# CW.net
KiCad netlist of a schematic drawn in Altium Designer
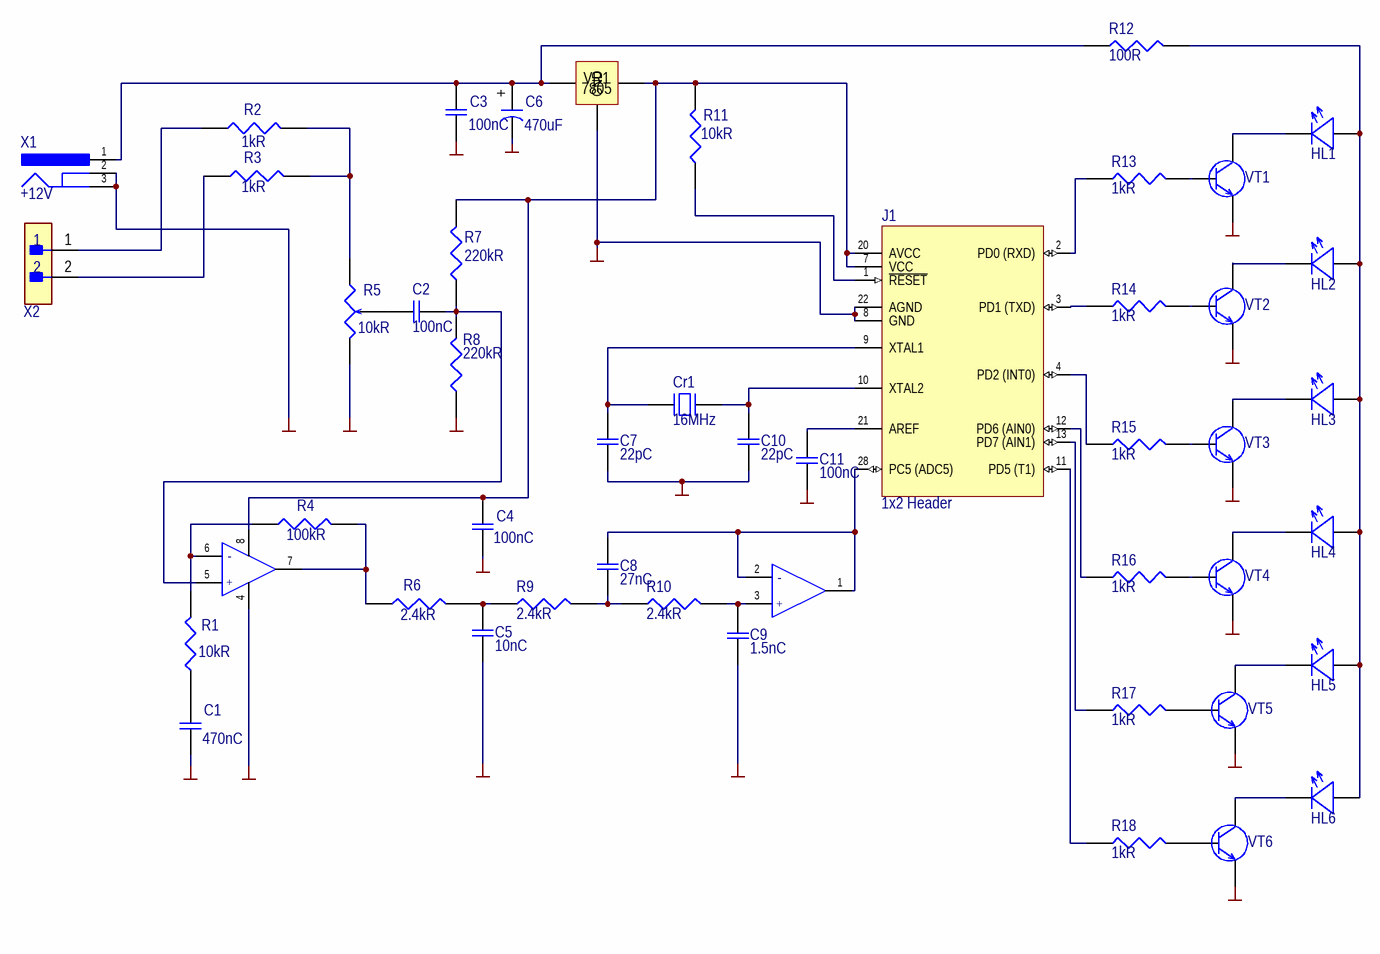
[diagram p0: CW.SchDoc]

(export (version "E")
  (design (tool "Eeschema 10.0.6"))
  (components
    (comp (ref "C1")
      (value "470nC")
      (footprint "C470nF")
      (description "CAP, X7R, 470NF, 16V, 0805, FULL REEL")
      (fields
        (field (name "MANUFACTURER") "Kyocera AVX")
        (field (name "MANUFACTURER PART NUMBER") "0805YC474KAT2A")
      )
      (libsource (lib "CW_Schlib") (part "C0805YC474KAT2A"))
    )
    (comp (ref "C2")
      (value "100nC")
      (footprint "C100nF")
      (description "CAP CER 0.1UF 16V 20% Y5V 0805")
      (fields
        (field (name "MANUFACTURER") "KEMET")
        (field (name "MANUFACTURER PART NUMBER") "C0805C104M4VACTU")
      )
      (libsource (lib "CW_Schlib") (part "C0805C104M4VACTU"))
    )
    (comp (ref "C3")
      (value "100nC")
      (footprint "C100nF")
      (description "CAP CER 0.1UF 16V 20% Y5V 0805")
      (fields
        (field (name "MANUFACTURER") "KEMET")
        (field (name "MANUFACTURER PART NUMBER") "C0805C104M4VACTU")
      )
      (libsource (lib "CW_Schlib") (part "C0805C104M4VACTU"))
    )
    (comp (ref "C4")
      (value "100nC")
      (footprint "C100nF")
      (description "CAP CER 0.1UF 16V 20% Y5V 0805")
      (fields
        (field (name "MANUFACTURER") "KEMET")
        (field (name "MANUFACTURER PART NUMBER") "C0805C104M4VACTU")
      )
      (libsource (lib "CW_Schlib") (part "C0805C104M4VACTU"))
    )
    (comp (ref "C5")
      (value "10nC")
      (footprint "C10nF")
      (description "CAP CER 10000PF 16V X7R 0402")
      (fields
        (field (name "MANUFACTURER") "Yageo")
        (field (name "MANUFACTURER PART NUMBER") "CC0402KRX7R7BB103")
      )
      (libsource (lib "CW_Schlib") (part "CC0402KRX7R7BB103"))
    )
    (comp (ref "C6")
      (value "470uF")
      (footprint "ElectrolyticCap")
      (fields
        (field (name "MANUFACTURER") "Panasonic")
        (field (name "MANUFACTURER PART NUMBER") "EEEFK1C471P")
        (field (name "TOLERANCE") "20%")
      )
      (libsource (lib "CW_Schlib") (part "EEEFK1C471P"))
    )
    (comp (ref "C7")
      (value "22pC")
      (footprint "C22pF")
      (description "1206 22pF Ceramic Multilayer Capacitor; 50VDC; 125degC; C0G Dielec; +/-5% SMD")
      (fields
        (field (name "MANUFACTURER") "KEMET")
        (field (name "MANUFACTURER PART NUMBER") "C1206C220J5GACTU")
      )
      (libsource (lib "CW_Schlib") (part "C1206C220J5GACTU"))
    )
    (comp (ref "C8")
      (value "27nC")
      (footprint "C27nF")
      (description "CAP CER 0.027UF 50V X7R 0805")
      (fields
        (field (name "MANUFACTURER") "KEMET")
        (field (name "MANUFACTURER PART NUMBER") "C0805C273K5RACTU")
      )
      (libsource (lib "CW_Schlib") (part "C0805C273K5RACTU"))
    )
    (comp (ref "C9")
      (value "1.5nC")
      (footprint "C1.5nF")
      (description "0805 1.5nF Ceramic Multilayer Capacitor,  100 VDC,  +125degC,  X7R Dielec,  +/-10%")
      (fields
        (field (name "MANUFACTURER") "Kyocera AVX")
        (field (name "MANUFACTURER PART NUMBER") "08051C152KAT2A")
      )
      (libsource (lib "CW_Schlib") (part "C08051C152KAT2A"))
    )
    (comp (ref "C10")
      (value "22pC")
      (footprint "C22pF")
      (description "1206 22pF Ceramic Multilayer Capacitor; 50VDC; 125degC; C0G Dielec; +/-5% SMD")
      (fields
        (field (name "MANUFACTURER") "KEMET")
        (field (name "MANUFACTURER PART NUMBER") "C1206C220J5GACTU")
      )
      (libsource (lib "CW_Schlib") (part "C1206C220J5GACTU"))
    )
    (comp (ref "C11")
      (value "100nC")
      (footprint "C100nF")
      (description "CAP CER 0.1UF 16V 20% Y5V 0805")
      (fields
        (field (name "MANUFACTURER") "KEMET")
        (field (name "MANUFACTURER PART NUMBER") "C0805C104M4VACTU")
      )
      (libsource (lib "CW_Schlib") (part "C0805C104M4VACTU"))
    )
    (comp (ref "Cr1")
      (value "16MHz")
      (footprint "Crystal")
      (description "CRYSTAL 16.0MHZ 20PF SMD")
      (fields (field (name "MANUFACTURER") "CTS") (field (name "MANUFACTURER PART NUMBER") "ATS16ASM-1"))
      (libsource (lib "CW_Schlib") (part "ATS16ASM-1"))
    )
    (comp (ref "DA1")
      (value "Amplifier (part B)")
      (footprint "LM358")
      (description "TEXAS INSTRUMENTS   LM358N/NOPB..   OP AMP, 1MHZ, 0.1V/S, 7MV, DIP8")
      (fields
        (field (name "MANUFACTURER") "TI National Semiconductor")
        (field (name "MANUFACTURER PART NUMBER") "LM358N/NOPB")
      )
      (libsource (lib "CW_Schlib") (part "LM358N/NOPB (1)"))
    )
    (comp (ref "DA2")
      (value "5V")
      (footprint "LM7805")
      (description "Series 3-Terminal Positive Regulators")
      (fields
        (field (name "MANUFACTURER") "Texas Instruments")
        (field (name "MANUFACTURER PART NUMBER") "LM7805CT/NOPB")
      )
      (libsource (lib "CW_Schlib") (part "LM7805CT/NOPB"))
    )
    (comp (ref "HL1")
      (value "red led")
      (footprint "LEDred")
      (description "WURTH ELEKTRONIK - 151051RS11000 - LED, Red, Through Hole, T-1 3/4 (5mm), 30 mA, 2.1 V, 630 nm")
      (fields
        (field (name "MANUFACTURER") "Wurth Electronics")
        (field (name "MANUFACTURER PART NUMBER") "151051RS11000")
      )
      (libsource (lib "CW_Schlib") (part "151051RS11000"))
    )
    (comp (ref "HL2")
      (value "blue led")
      (footprint "LEDblue")
      (description "WURTH ELEKTRONIK - 151051BS04000 - LED, 5MM, BLUE, 500MCD, 470NM")
      (fields
        (field (name "MANUFACTURER") "Wurth Electronics")
        (field (name "MANUFACTURER PART NUMBER") "151051BS04000")
      )
      (libsource (lib "CW_Schlib") (part "151051BS04000"))
    )
    (comp (ref "HL3")
      (value "red led")
      (footprint "LEDred")
      (description "WURTH ELEKTRONIK - 151051RS11000 - LED, Red, Through Hole, T-1 3/4 (5mm), 30 mA, 2.1 V, 630 nm")
      (fields
        (field (name "MANUFACTURER") "Wurth Electronics")
        (field (name "MANUFACTURER PART NUMBER") "151051RS11000")
      )
      (libsource (lib "CW_Schlib") (part "151051RS11000"))
    )
    (comp (ref "HL4")
      (value "green led")
      (footprint "LEDgreen")
      (description "WURTH ELEKTRONIK - 151051VS04000 - LED, Green, Through Hole, T-1 3/4 (5mm), 30 mA, 2.1 V, 572 nm")
      (fields
        (field (name "MANUFACTURER") "Wurth Electronics")
        (field (name "MANUFACTURER PART NUMBER") "151051VS04000")
      )
      (libsource (lib "CW_Schlib") (part "151051VS04000"))
    )
    (comp (ref "HL5")
      (value "yellow led")
      (footprint "LEDyellow")
      (description "WURTH ELEKTRONIK - 151051YS04000 - LED, Yellow, Through Hole, T-1 3/4 (5mm), 30 mA, 2 V, 590 nm")
      (fields
        (field (name "MANUFACTURER") "Wurth Electronics")
        (field (name "MANUFACTURER PART NUMBER") "151051YS04000")
      )
      (libsource (lib "CW_Schlib") (part "151051YS04000"))
    )
    (comp (ref "HL6")
      (value "green led")
      (footprint "LEDgreen")
      (description "WURTH ELEKTRONIK - 151051VS04000 - LED, Green, Through Hole, T-1 3/4 (5mm), 30 mA, 2.1 V, 572 nm")
      (fields
        (field (name "MANUFACTURER") "Wurth Electronics")
        (field (name "MANUFACTURER PART NUMBER") "151051VS04000")
      )
      (libsource (lib "CW_Schlib") (part "151051VS04000"))
    )
    (comp (ref "J1")
      (value "1x2 Header")
      (footprint "ATmega8")
      (description "MCU 8-bit ATmega AVR RISC 8KB Flash 3.3V/5V 28-Pin PDIP")
      (fields
        (field (name "MANUFACTURER") "Microchip / Atmel")
        (field (name "MANUFACTURER PART NUMBER") "ATMEGA8A-PU")
      )
      (libsource (lib "CW_Schlib") (part "ATMEGA8A-PU"))
    )
    (comp (ref "R1")
      (value "10kR")
      (footprint "R10kOhm")
      (description "Res Thick Film 0805 10K Ohm 5% 1/8W ±200ppm/°C Molded SMD Paper T/R")
      (fields
        (field (name "MANUFACTURER") "Vishay Semiconductors")
        (field (name "MANUFACTURER PART NUMBER") "CRCW080510K0JNEAC")
      )
      (libsource (lib "CW_Schlib") (part "CRCW080510K0JNEAC"))
    )
    (comp (ref "R2")
      (value "1kR")
      (footprint "R1kOhm")
      (description "Res Thick Film 0805 1K Ohm 5% 1/8W 200ppm/C Molded SMD SMD Paper T/R")
      (fields
        (field (name "MANUFACTURER") "Vishay Dale")
        (field (name "MANUFACTURER PART NUMBER") "CRCW08051K00JNEA")
      )
      (libsource (lib "CW_Schlib") (part "CRCW08051K00JNEA"))
    )
    (comp (ref "R3")
      (value "1kR")
      (footprint "R1kOhm")
      (description "Res Thick Film 0805 1K Ohm 5% 1/8W 200ppm/C Molded SMD SMD Paper T/R")
      (fields
        (field (name "MANUFACTURER") "Vishay Dale")
        (field (name "MANUFACTURER PART NUMBER") "CRCW08051K00JNEA")
      )
      (libsource (lib "CW_Schlib") (part "CRCW08051K00JNEA"))
    )
    (comp (ref "R4")
      (value "100kR")
      (footprint "R100kOhm")
      (description "Res Thick Film 0805 100K Ohm 5% 1/8W 200ppm/C Molded SMD SMD Paper T/R")
      (fields
        (field (name "MANUFACTURER") "Vishay Dale")
        (field (name "MANUFACTURER PART NUMBER") "CRCW0805100KJNEB")
      )
      (libsource (lib "CW_Schlib") (part "CRCW0805100KJNEB"))
    )
    (comp (ref "R5")
      (value "10kR")
      (footprint "Potentiometer")
      (description "BOURNS 3313J-1-103E             TRIMMER, 10KOHM, 125mW, SMD")
      (fields (field (name "MANUFACTURER") "Bourns") (field (name "MANUFACTURER PART NUMBER") "3313J-1-103E"))
      (libsource (lib "CW_Schlib") (part "3313J-1-103E"))
    )
    (comp (ref "R6")
      (value "2.4kR")
      (footprint "R2.4kohm")
      (description "Resistor,Metal Glaze,2.4KOhms,150WV,5+/-% Tol,-200,200ppm-TC,0805-Case ;RoHS Compliant: Yes")
      (fields
        (field (name "MANUFACTURER") "Vishay Dale")
        (field (name "MANUFACTURER PART NUMBER") "CRCW08052K40JNEA")
      )
      (libsource (lib "CW_Schlib") (part "CRCW08052K40JNEA"))
    )
    (comp (ref "R7")
      (value "220kR")
      (footprint "R220kOhm")
      (description "RES SMD 220K OHM 5% 1/8W 0805")
      (fields
        (field (name "MANUFACTURER") "Vishay Dale")
        (field (name "MANUFACTURER PART NUMBER") "CRCW0805220KJNEA")
      )
      (libsource (lib "CW_Schlib") (part "CRCW0805220KJNEA"))
    )
    (comp (ref "R8")
      (value "220kR")
      (footprint "R220kOhm")
      (description "RES SMD 220K OHM 5% 1/8W 0805")
      (fields
        (field (name "MANUFACTURER") "Vishay Dale")
        (field (name "MANUFACTURER PART NUMBER") "CRCW0805220KJNEA")
      )
      (libsource (lib "CW_Schlib") (part "CRCW0805220KJNEA"))
    )
    (comp (ref "R9")
      (value "2.4kR")
      (footprint "R2.4kohm")
      (description "Resistor,Metal Glaze,2.4KOhms,150WV,5+/-% Tol,-200,200ppm-TC,0805-Case ;RoHS Compliant: Yes")
      (fields
        (field (name "MANUFACTURER") "Vishay Dale")
        (field (name "MANUFACTURER PART NUMBER") "CRCW08052K40JNEA")
      )
      (libsource (lib "CW_Schlib") (part "CRCW08052K40JNEA"))
    )
    (comp (ref "R10")
      (value "2.4kR")
      (footprint "R2.4kohm")
      (description "Resistor,Metal Glaze,2.4KOhms,150WV,5+/-% Tol,-200,200ppm-TC,0805-Case ;RoHS Compliant: Yes")
      (fields
        (field (name "MANUFACTURER") "Vishay Dale")
        (field (name "MANUFACTURER PART NUMBER") "CRCW08052K40JNEA")
      )
      (libsource (lib "CW_Schlib") (part "CRCW08052K40JNEA"))
    )
    (comp (ref "R11")
      (value "10kR")
      (footprint "R10kOhm")
      (description "Res Thick Film 0805 10K Ohm 5% 1/8W ±200ppm/°C Molded SMD Paper T/R")
      (fields
        (field (name "MANUFACTURER") "Vishay Semiconductors")
        (field (name "MANUFACTURER PART NUMBER") "CRCW080510K0JNEAC")
      )
      (libsource (lib "CW_Schlib") (part "CRCW080510K0JNEAC"))
    )
    (comp (ref "R12")
      (value "100R")
      (footprint "R100Ohm")
      (fields
        (field (name "MANUFACTURER") "Panasonic")
        (field (name "MANUFACTURER PART NUMBER") "ERA-6AEB101V")
        (field (name "TOLERANCE") "0.1%")
      )
      (libsource (lib "CW_Schlib") (part "ERA-6AEB101V"))
    )
    (comp (ref "R13")
      (value "1kR")
      (footprint "R1kOhm")
      (description "Res Thick Film 0805 1K Ohm 5% 1/8W 200ppm/C Molded SMD SMD Paper T/R")
      (fields
        (field (name "MANUFACTURER") "Vishay Dale")
        (field (name "MANUFACTURER PART NUMBER") "CRCW08051K00JNEA")
      )
      (libsource (lib "CW_Schlib") (part "CRCW08051K00JNEA"))
    )
    (comp (ref "R14")
      (value "1kR")
      (footprint "R1kOhm")
      (description "Res Thick Film 0805 1K Ohm 5% 1/8W 200ppm/C Molded SMD SMD Paper T/R")
      (fields
        (field (name "MANUFACTURER") "Vishay Dale")
        (field (name "MANUFACTURER PART NUMBER") "CRCW08051K00JNEA")
      )
      (libsource (lib "CW_Schlib") (part "CRCW08051K00JNEA"))
    )
    (comp (ref "R15")
      (value "1kR")
      (footprint "R1kOhm")
      (description "Res Thick Film 0805 1K Ohm 5% 1/8W 200ppm/C Molded SMD SMD Paper T/R")
      (fields
        (field (name "MANUFACTURER") "Vishay Dale")
        (field (name "MANUFACTURER PART NUMBER") "CRCW08051K00JNEA")
      )
      (libsource (lib "CW_Schlib") (part "CRCW08051K00JNEA"))
    )
    (comp (ref "R16")
      (value "1kR")
      (footprint "R1kOhm")
      (description "Res Thick Film 0805 1K Ohm 5% 1/8W 200ppm/C Molded SMD SMD Paper T/R")
      (fields
        (field (name "MANUFACTURER") "Vishay Dale")
        (field (name "MANUFACTURER PART NUMBER") "CRCW08051K00JNEA")
      )
      (libsource (lib "CW_Schlib") (part "CRCW08051K00JNEA"))
    )
    (comp (ref "R17")
      (value "1kR")
      (footprint "R1kOhm")
      (description "Res Thick Film 0805 1K Ohm 5% 1/8W 200ppm/C Molded SMD SMD Paper T/R")
      (fields
        (field (name "MANUFACTURER") "Vishay Dale")
        (field (name "MANUFACTURER PART NUMBER") "CRCW08051K00JNEA")
      )
      (libsource (lib "CW_Schlib") (part "CRCW08051K00JNEA"))
    )
    (comp (ref "R18")
      (value "1kR")
      (footprint "R1kOhm")
      (description "Res Thick Film 0805 1K Ohm 5% 1/8W 200ppm/C Molded SMD SMD Paper T/R")
      (fields
        (field (name "MANUFACTURER") "Vishay Dale")
        (field (name "MANUFACTURER PART NUMBER") "CRCW08051K00JNEA")
      )
      (libsource (lib "CW_Schlib") (part "CRCW08051K00JNEA"))
    )
    (comp (ref "VT1")
      (value "BC639")
      (footprint "BC639")
      (description "TRANS NPN 80V 1A TO-92")
      (fields (field (name "MANUFACTURER") "ON Semiconductor / Fairchild"))
      (libsource (lib "CW_Schlib") (part "BC639"))
    )
    (comp (ref "VT2")
      (value "BC639")
      (footprint "BC639")
      (description "TRANS NPN 80V 1A TO-92")
      (fields (field (name "MANUFACTURER") "ON Semiconductor / Fairchild"))
      (libsource (lib "CW_Schlib") (part "BC639"))
    )
    (comp (ref "VT3")
      (value "BC639")
      (footprint "BC639")
      (description "TRANS NPN 80V 1A TO-92")
      (fields (field (name "MANUFACTURER") "ON Semiconductor / Fairchild"))
      (libsource (lib "CW_Schlib") (part "BC639"))
    )
    (comp (ref "VT4")
      (value "BC639")
      (footprint "BC639")
      (description "TRANS NPN 80V 1A TO-92")
      (fields (field (name "MANUFACTURER") "ON Semiconductor / Fairchild"))
      (libsource (lib "CW_Schlib") (part "BC639"))
    )
    (comp (ref "VT5")
      (value "BC639")
      (footprint "BC639")
      (description "TRANS NPN 80V 1A TO-92")
      (fields (field (name "MANUFACTURER") "ON Semiconductor / Fairchild"))
      (libsource (lib "CW_Schlib") (part "BC639"))
    )
    (comp (ref "VT6")
      (value "BC639")
      (footprint "BC639")
      (description "TRANS NPN 80V 1A TO-92")
      (fields (field (name "MANUFACTURER") "ON Semiconductor / Fairchild"))
      (libsource (lib "CW_Schlib") (part "BC639"))
    )
    (comp (ref "X1")
      (value "+12V")
      (footprint "PG_Connector")
      (description "KYCON - KLDX-0202-A - DC Power Connector, Jack, 3.5 A, 2 mm, PCB Mount, Through Hole")
      (fields (field (name "MANUFACTURER") "Kycon") (field (name "MANUFACTURER PART NUMBER") "KLDX-0202-A"))
      (libsource (lib "CW_Schlib") (part "KLDX-0202-A"))
    )
    (comp (ref "X2")
      (value "ConnectorAudio")
      (footprint "AudioConnector")
      (fields (field (name "MANUFACTURER") "Molex") (field (name "MANUFACTURER PART NUMBER") "43650-0229"))
      (libsource (lib "CW_Schlib") (part "43650-0229"))
    )
  )
  (nets
    (net (code "1") (name "GND") (class "Default")
      (node (ref "C1") (pin "1") (pinfunction "1_1") (pintype "passive"))
      (node (ref "C10") (pin "1") (pinfunction "1_1") (pintype "passive"))
      (node (ref "C11") (pin "1") (pinfunction "1_1") (pintype "passive"))
      (node (ref "C3") (pin "1") (pinfunction "1_1") (pintype "passive"))
      (node (ref "C4") (pin "1") (pinfunction "1_1") (pintype "passive"))
      (node (ref "C5") (pin "1") (pinfunction "1_1") (pintype "passive"))
      (node (ref "C6") (pin "-") (pinfunction "1_-") (pintype "passive"))
      (node (ref "C7") (pin "1") (pinfunction "1_1") (pintype "passive"))
      (node (ref "C9") (pin "1") (pinfunction "1_1") (pintype "passive"))
      (node (ref "DA1") (pin "4") (pinfunction "GND_4") (pintype "passive"))
      (node (ref "DA2") (pin "3") (pinfunction "GND_3") (pintype "passive"))
      (node (ref "J1") (pin "22") (pinfunction "AGND_22") (pintype "power_in"))
      (node (ref "J1") (pin "8") (pinfunction "GND_8") (pintype "power_in"))
      (node (ref "R5") (pin "2") (pinfunction "2_2") (pintype "passive"))
      (node (ref "R8") (pin "1") (pinfunction "1_1") (pintype "passive"))
      (node (ref "VT1") (pin "3") (pinfunction "GND_3") (pintype "passive"))
      (node (ref "VT2") (pin "3") (pinfunction "GND_3") (pintype "passive"))
      (node (ref "VT3") (pin "3") (pinfunction "GND_3") (pintype "passive"))
      (node (ref "VT4") (pin "3") (pinfunction "GND_3") (pintype "passive"))
      (node (ref "VT5") (pin "3") (pinfunction "GND_3") (pintype "passive"))
      (node (ref "VT6") (pin "3") (pinfunction "GND_3") (pintype "passive"))
      (node (ref "X1") (pin "2") (pinfunction "2_2") (pintype "passive"))
      (node (ref "X1") (pin "3") (pinfunction "GND_3") (pintype "passive"))
    )
    (net (code "2") (name "Net-(C1-Pad2)") (class "Default")
      (node (ref "C1") (pin "2") (pinfunction "2_2") (pintype "passive"))
      (node (ref "R1") (pin "1") (pinfunction "1_1") (pintype "passive"))
    )
    (net (code "3") (name "Net-(C2-Pad1)") (class "Default")
      (node (ref "C2") (pin "1") (pinfunction "1_1") (pintype "passive"))
      (node (ref "R5") (pin "3") (pinfunction "3_3") (pintype "passive"))
    )
    (net (code "4") (name "Net-(C5-Pad2)") (class "Default")
      (node (ref "C5") (pin "2") (pinfunction "2_2") (pintype "passive"))
      (node (ref "R9") (pin "1") (pinfunction "1_1") (pintype "passive"))
    )
    (net (code "5") (name "Net-(C6-2)") (class "Default")
      (node (ref "C3") (pin "2") (pinfunction "2_2") (pintype "passive"))
      (node (ref "C6") (pin "+") (pinfunction "2_+") (pintype "passive"))
      (node (ref "DA2") (pin "1") (pinfunction "Input_1") (pintype "passive"))
      (node (ref "R12") (pin "1") (pinfunction "1_1") (pintype "passive"))
      (node (ref "X1") (pin "1") (pinfunction "PWR_1") (pintype "passive"))
    )
    (net (code "6") (name "Net-(C8-Pad1)") (class "Default")
      (node (ref "C8") (pin "1") (pinfunction "1_1") (pintype "passive"))
      (node (ref "R10") (pin "1") (pinfunction "1_1") (pintype "passive"))
      (node (ref "R9") (pin "2") (pinfunction "2_2") (pintype "passive"))
    )
    (net (code "7") (name "Net-(DA1A-+)") (class "Default")
      (node (ref "C9") (pin "2") (pinfunction "2_2") (pintype "passive"))
      (node (ref "DA1") (pin "3") (pinfunction "+_3") (pintype "passive"))
      (node (ref "R10") (pin "2") (pinfunction "2_2") (pintype "passive"))
    )
    (net (code "8") (name "Net-(DA1A--)") (class "Default")
      (node (ref "C8") (pin "2") (pinfunction "2_2") (pintype "passive"))
      (node (ref "DA1") (pin "1") (pinfunction "OUT_A_1") (pintype "passive"))
      (node (ref "DA1") (pin "2") (pinfunction "-_2") (pintype "passive"))
      (node (ref "J1") (pin "28") (pinfunction "PC5_(ADC5)_28") (pintype "bidirectional"))
    )
    (net (code "9") (name "Net-(DA1B-+)") (class "Default")
      (node (ref "C2") (pin "2") (pinfunction "2_2") (pintype "passive"))
      (node (ref "DA1") (pin "5") (pinfunction "+_5") (pintype "passive"))
      (node (ref "R7") (pin "1") (pinfunction "1_1") (pintype "passive"))
      (node (ref "R8") (pin "2") (pinfunction "2_2") (pintype "passive"))
    )
    (net (code "10") (name "Net-(DA1B--)") (class "Default")
      (node (ref "DA1") (pin "6") (pinfunction "-_6") (pintype "passive"))
      (node (ref "R1") (pin "2") (pinfunction "2_2") (pintype "passive"))
      (node (ref "R4") (pin "1") (pinfunction "1_1") (pintype "passive"))
    )
    (net (code "11") (name "Net-(DA1B-OUT_B)") (class "Default")
      (node (ref "DA1") (pin "7") (pinfunction "OUT_B_7") (pintype "passive"))
      (node (ref "R4") (pin "2") (pinfunction "2_2") (pintype "passive"))
      (node (ref "R6") (pin "1") (pinfunction "1_1") (pintype "passive"))
    )
    (net (code "12") (name "Net-(DA1B-VCC)") (class "Default")
      (node (ref "C4") (pin "2") (pinfunction "2_2") (pintype "passive"))
      (node (ref "DA1") (pin "8") (pinfunction "VCC_8") (pintype "passive"))
      (node (ref "DA2") (pin "2") (pinfunction "Output_2") (pintype "passive"))
      (node (ref "J1") (pin "20") (pinfunction "AVCC_20") (pintype "power_in"))
      (node (ref "J1") (pin "7") (pinfunction "VCC_7") (pintype "power_in"))
      (node (ref "R11") (pin "2") (pinfunction "2_2") (pintype "passive"))
      (node (ref "R7") (pin "2") (pinfunction "2_2") (pintype "passive"))
    )
    (net (code "13") (name "Net-(HL1-+)") (class "Default")
      (node (ref "HL1") (pin "2") (pinfunction "+_2") (pintype "passive"))
      (node (ref "HL2") (pin "2") (pinfunction "+_2") (pintype "passive"))
      (node (ref "HL3") (pin "2") (pinfunction "+_2") (pintype "passive"))
      (node (ref "HL4") (pin "2") (pinfunction "+_2") (pintype "passive"))
      (node (ref "HL5") (pin "2") (pinfunction "+_2") (pintype "passive"))
      (node (ref "HL6") (pin "2") (pinfunction "+_2") (pintype "passive"))
      (node (ref "R12") (pin "2") (pinfunction "2_2") (pintype "passive"))
    )
    (net (code "14") (name "Net-(HL1--)") (class "Default")
      (node (ref "HL1") (pin "1") (pinfunction "-_1") (pintype "passive"))
      (node (ref "VT1") (pin "2") (pinfunction "2_2") (pintype "passive"))
    )
    (net (code "15") (name "Net-(HL2--)") (class "Default")
      (node (ref "HL2") (pin "1") (pinfunction "-_1") (pintype "passive"))
      (node (ref "VT2") (pin "2") (pinfunction "2_2") (pintype "passive"))
    )
    (net (code "16") (name "Net-(HL3--)") (class "Default")
      (node (ref "HL3") (pin "1") (pinfunction "-_1") (pintype "passive"))
      (node (ref "VT3") (pin "2") (pinfunction "2_2") (pintype "passive"))
    )
    (net (code "17") (name "Net-(HL4--)") (class "Default")
      (node (ref "HL4") (pin "1") (pinfunction "-_1") (pintype "passive"))
      (node (ref "VT4") (pin "2") (pinfunction "2_2") (pintype "passive"))
    )
    (net (code "18") (name "Net-(HL5--)") (class "Default")
      (node (ref "HL5") (pin "1") (pinfunction "-_1") (pintype "passive"))
      (node (ref "VT5") (pin "2") (pinfunction "2_2") (pintype "passive"))
    )
    (net (code "19") (name "Net-(HL6--)") (class "Default")
      (node (ref "HL6") (pin "1") (pinfunction "-_1") (pintype "passive"))
      (node (ref "VT6") (pin "2") (pinfunction "2_2") (pintype "passive"))
    )
    (net (code "20") (name "Net-(J1-AREF)") (class "Default")
      (node (ref "C11") (pin "2") (pinfunction "2_2") (pintype "passive"))
      (node (ref "J1") (pin "21") (pinfunction "AREF_21") (pintype "passive"))
    )
    (net (code "21") (name "Net-(J1-PD0_(RXD))") (class "Default")
      (node (ref "J1") (pin "2") (pinfunction "PD0_(RXD)_2") (pintype "bidirectional"))
      (node (ref "R13") (pin "1") (pinfunction "1_1") (pintype "passive"))
    )
    (net (code "22") (name "Net-(J1-PD1_(TXD))") (class "Default")
      (node (ref "J1") (pin "3") (pinfunction "PD1_(TXD)_3") (pintype "bidirectional"))
      (node (ref "R14") (pin "1") (pinfunction "1_1") (pintype "passive"))
    )
    (net (code "23") (name "Net-(J1-PD2_(INT0))") (class "Default")
      (node (ref "J1") (pin "4") (pinfunction "PD2_(INT0)_4") (pintype "bidirectional"))
      (node (ref "R15") (pin "1") (pinfunction "1_1") (pintype "passive"))
    )
    (net (code "24") (name "Net-(J1-PD5_(T1))") (class "Default")
      (node (ref "J1") (pin "11") (pinfunction "PD5_(T1)_11") (pintype "bidirectional"))
      (node (ref "R18") (pin "1") (pinfunction "1_1") (pintype "passive"))
    )
    (net (code "25") (name "Net-(J1-PD6_(AIN0))") (class "Default")
      (node (ref "J1") (pin "12") (pinfunction "PD6_(AIN0)_12") (pintype "bidirectional"))
      (node (ref "R16") (pin "1") (pinfunction "1_1") (pintype "passive"))
    )
    (net (code "26") (name "Net-(J1-PD7_(AIN1))") (class "Default")
      (node (ref "J1") (pin "13") (pinfunction "PD7_(AIN1)_13") (pintype "bidirectional"))
      (node (ref "R17") (pin "1") (pinfunction "1_1") (pintype "passive"))
    )
    (net (code "27") (name "Net-(J1-XTAL1)") (class "Default")
      (node (ref "C7") (pin "2") (pinfunction "2_2") (pintype "passive"))
      (node (ref "Cr1") (pin "1") (pinfunction "1_1") (pintype "passive"))
      (node (ref "J1") (pin "9") (pinfunction "XTAL1_9") (pintype "passive"))
    )
    (net (code "28") (name "Net-(J1-XTAL2)") (class "Default")
      (node (ref "C10") (pin "2") (pinfunction "2_2") (pintype "passive"))
      (node (ref "Cr1") (pin "2") (pinfunction "2_2") (pintype "passive"))
      (node (ref "J1") (pin "10") (pinfunction "XTAL2_10") (pintype "passive"))
    )
    (net (code "29") (name "Net-(J1-~{RESET})") (class "Default")
      (node (ref "J1") (pin "1") (pinfunction "~{RESET}_1") (pintype "input"))
      (node (ref "R11") (pin "1") (pinfunction "1_1") (pintype "passive"))
    )
    (net (code "30") (name "Net-(R2-Pad1)") (class "Default")
      (node (ref "R2") (pin "1") (pinfunction "1_1") (pintype "passive"))
      (node (ref "X2") (pin "1") (pinfunction "1_1") (pintype "passive"))
    )
    (net (code "31") (name "Net-(R2-Pad2)") (class "Default")
      (node (ref "R2") (pin "2") (pinfunction "2_2") (pintype "passive"))
      (node (ref "R3") (pin "2") (pinfunction "2_2") (pintype "passive"))
      (node (ref "R5") (pin "1") (pinfunction "1_1") (pintype "passive"))
    )
    (net (code "32") (name "Net-(R3-Pad1)") (class "Default")
      (node (ref "R3") (pin "1") (pinfunction "1_1") (pintype "passive"))
      (node (ref "X2") (pin "2") (pinfunction "2_2") (pintype "passive"))
    )
    (net (code "33") (name "Net-(R13-Pad2)") (class "Default")
      (node (ref "R13") (pin "2") (pinfunction "2_2") (pintype "passive"))
      (node (ref "VT1") (pin "1") (pinfunction "1_1") (pintype "passive"))
    )
    (net (code "34") (name "Net-(R14-Pad2)") (class "Default")
      (node (ref "R14") (pin "2") (pinfunction "2_2") (pintype "passive"))
      (node (ref "VT2") (pin "1") (pinfunction "1_1") (pintype "passive"))
    )
    (net (code "35") (name "Net-(R15-Pad2)") (class "Default")
      (node (ref "R15") (pin "2") (pinfunction "2_2") (pintype "passive"))
      (node (ref "VT3") (pin "1") (pinfunction "1_1") (pintype "passive"))
    )
    (net (code "36") (name "Net-(R16-Pad2)") (class "Default")
      (node (ref "R16") (pin "2") (pinfunction "2_2") (pintype "passive"))
      (node (ref "VT4") (pin "1") (pinfunction "1_1") (pintype "passive"))
    )
    (net (code "37") (name "Net-(R17-Pad2)") (class "Default")
      (node (ref "R17") (pin "2") (pinfunction "2_2") (pintype "passive"))
      (node (ref "VT5") (pin "1") (pinfunction "1_1") (pintype "passive"))
    )
    (net (code "38") (name "Net-(R18-Pad2)") (class "Default")
      (node (ref "R18") (pin "2") (pinfunction "2_2") (pintype "passive"))
      (node (ref "VT6") (pin "1") (pinfunction "1_1") (pintype "passive"))
    )
    (net (code "39") (name "unconnected-(R6-Pad2)") (class "Default")
      (node (ref "R6") (pin "2") (pinfunction "2_2") (pintype "passive"))
    )
  )
)
